# remotetool.net
KiCad netlist of a schematic drawn in EAGLE
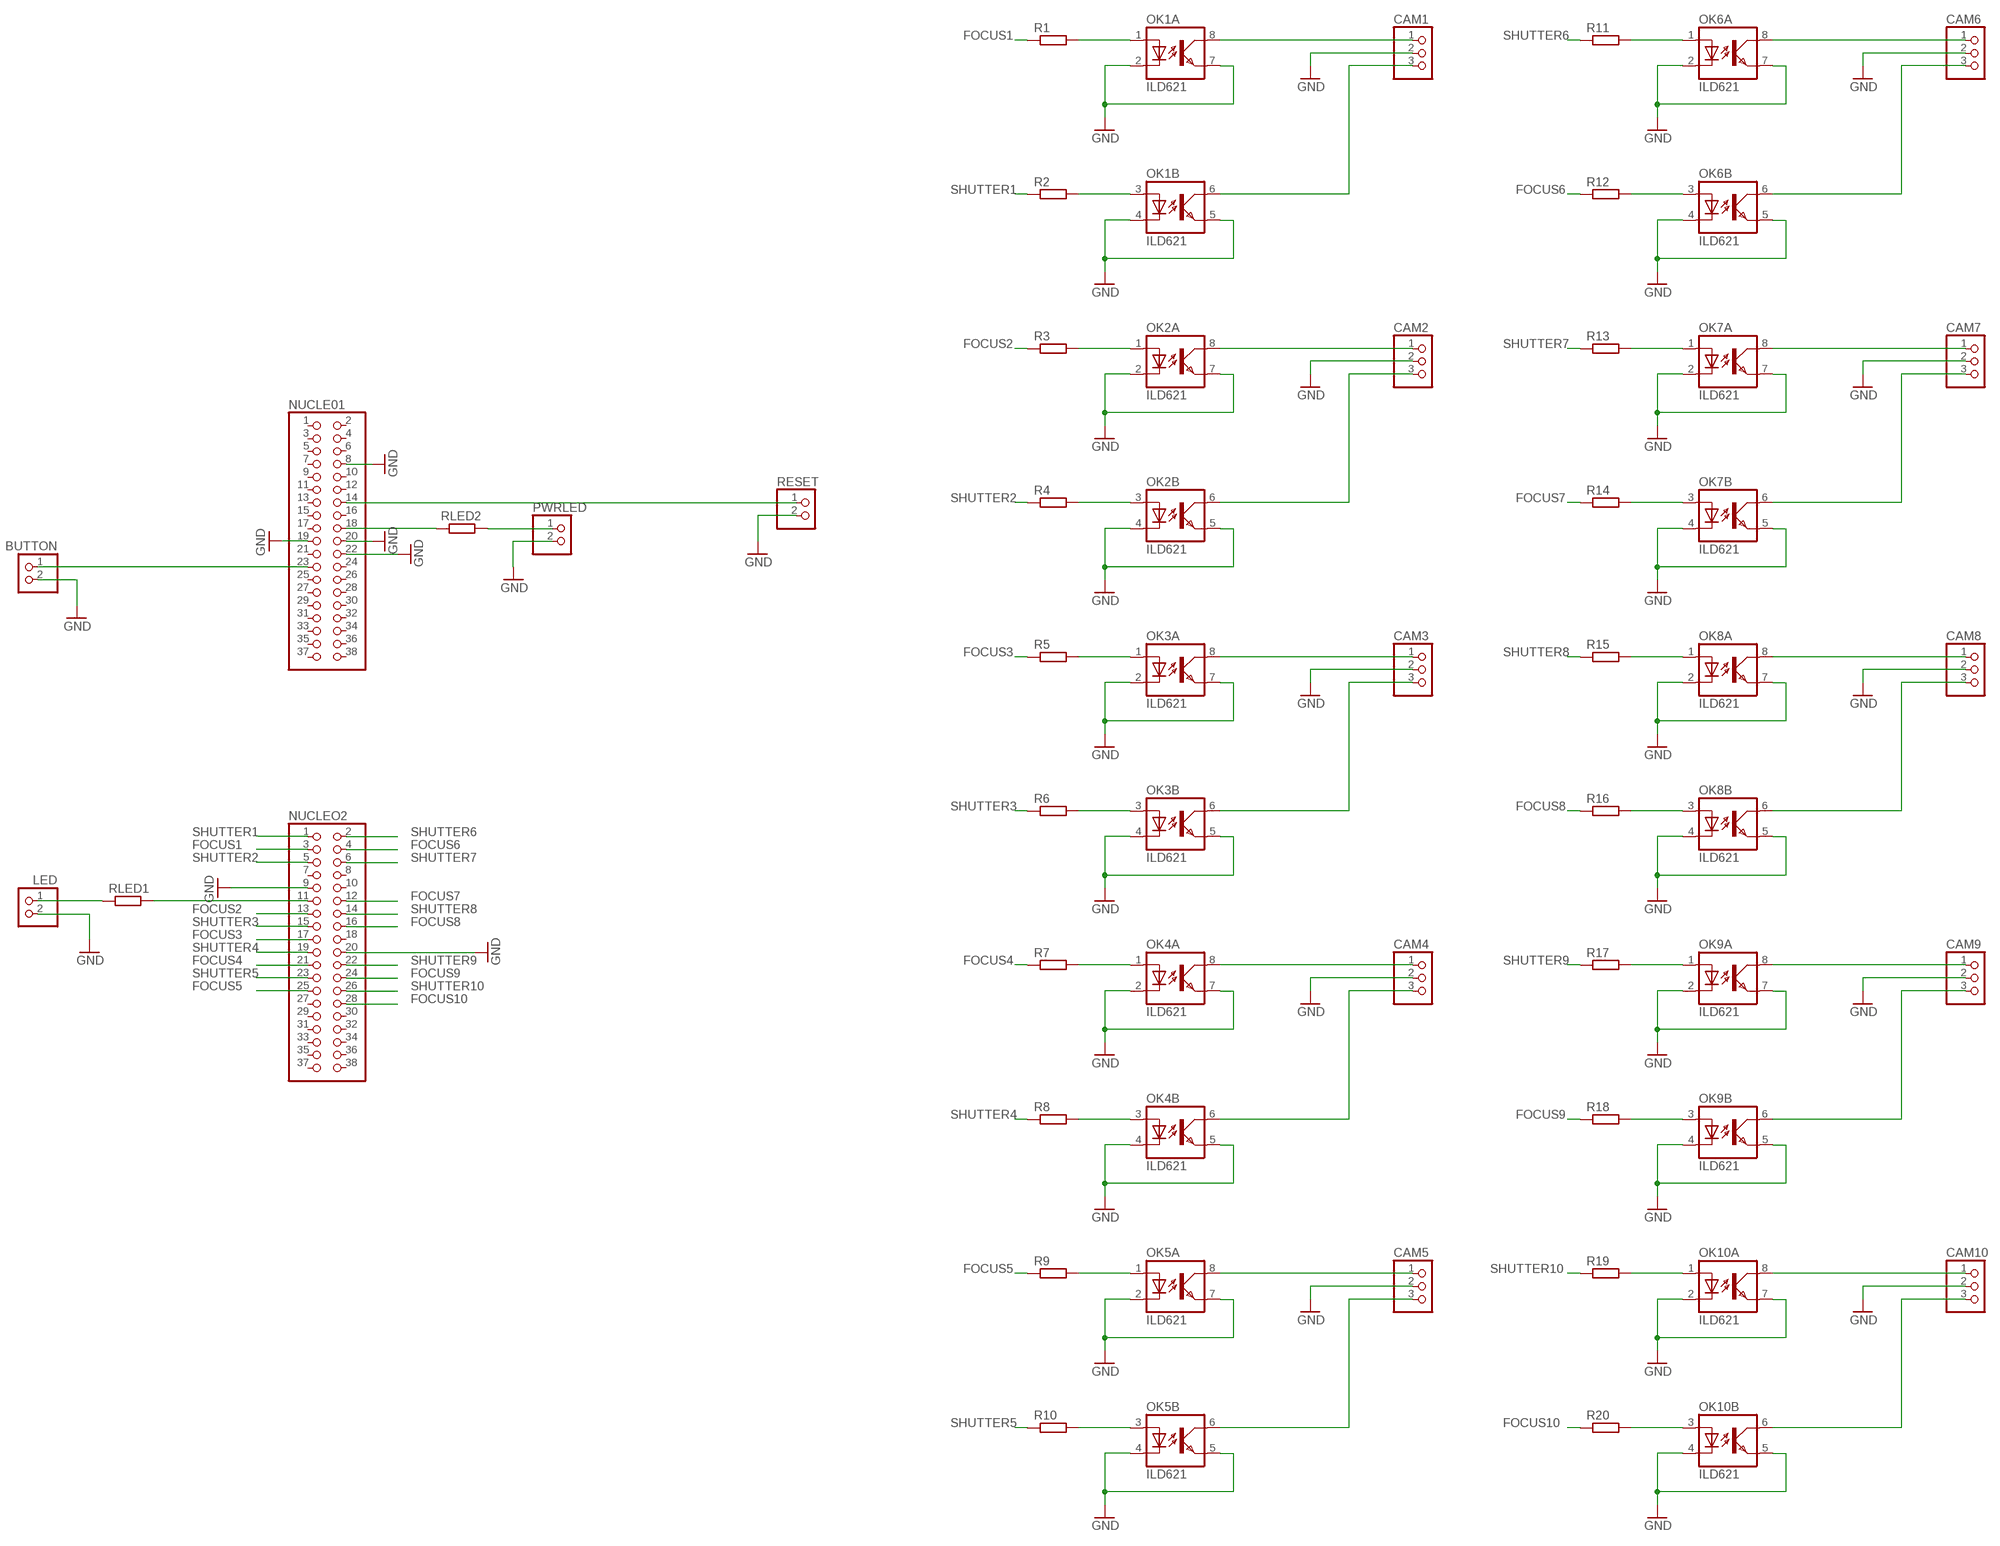
[diagram p0: schematic, sheet 1]

(export (version "E")
  (design (tool "Eeschema 10.0.6"))
  (components
    (comp (ref "BUTTON")
      (value "PINHD-1X2")
      (footprint "eagle-import:1X02")
      (libsource (lib "eagle-import") (part "PINHD-1X2"))
    )
    (comp (ref "CAM1")
      (value "PINHD-1X3")
      (footprint "eagle-import:1X03")
      (libsource (lib "eagle-import") (part "PINHD-1X3"))
    )
    (comp (ref "CAM2")
      (value "PINHD-1X3")
      (footprint "eagle-import:1X03")
      (libsource (lib "eagle-import") (part "PINHD-1X3"))
    )
    (comp (ref "CAM3")
      (value "PINHD-1X3")
      (footprint "eagle-import:1X03")
      (libsource (lib "eagle-import") (part "PINHD-1X3"))
    )
    (comp (ref "CAM4")
      (value "PINHD-1X3")
      (footprint "eagle-import:1X03")
      (libsource (lib "eagle-import") (part "PINHD-1X3"))
    )
    (comp (ref "CAM5")
      (value "PINHD-1X3")
      (footprint "eagle-import:1X03")
      (libsource (lib "eagle-import") (part "PINHD-1X3"))
    )
    (comp (ref "CAM6")
      (value "PINHD-1X3")
      (footprint "eagle-import:1X03")
      (libsource (lib "eagle-import") (part "PINHD-1X3"))
    )
    (comp (ref "CAM7")
      (value "PINHD-1X3")
      (footprint "eagle-import:1X03")
      (libsource (lib "eagle-import") (part "PINHD-1X3"))
    )
    (comp (ref "CAM8")
      (value "PINHD-1X3")
      (footprint "eagle-import:1X03")
      (libsource (lib "eagle-import") (part "PINHD-1X3"))
    )
    (comp (ref "CAM9")
      (value "PINHD-1X3")
      (footprint "eagle-import:1X03")
      (libsource (lib "eagle-import") (part "PINHD-1X3"))
    )
    (comp (ref "CAM10")
      (value "PINHD-1X3")
      (footprint "eagle-import:1X03")
      (libsource (lib "eagle-import") (part "PINHD-1X3"))
    )
    (comp (ref "LED")
      (value "PINHD-1X2")
      (footprint "eagle-import:1X02")
      (libsource (lib "eagle-import") (part "PINHD-1X2"))
    )
    (comp (ref "NUCLE01")
      (value "PINHD-2X19")
      (footprint "eagle-import:2X19")
      (libsource (lib "eagle-import") (part "PINHD-2X19"))
    )
    (comp (ref "NUCLEO2")
      (value "PINHD-2X19")
      (footprint "eagle-import:2X19")
      (libsource (lib "eagle-import") (part "PINHD-2X19"))
    )
    (comp (ref "OK1")
      (value "ILD621")
      (footprint "eagle-import:DIL08")
      (fields (field (name "MF") "VISHAY/TELEFUNKEN"))
      (libsource (lib "eagle-import") (part "ILD621"))
    )
    (comp (ref "OK2")
      (value "ILD621")
      (footprint "eagle-import:DIL08")
      (fields (field (name "MF") "VISHAY/TELEFUNKEN"))
      (libsource (lib "eagle-import") (part "ILD621"))
    )
    (comp (ref "OK3")
      (value "ILD621")
      (footprint "eagle-import:DIL08")
      (fields (field (name "MF") "VISHAY/TELEFUNKEN"))
      (libsource (lib "eagle-import") (part "ILD621"))
    )
    (comp (ref "OK4")
      (value "ILD621")
      (footprint "eagle-import:DIL08")
      (fields (field (name "MF") "VISHAY/TELEFUNKEN"))
      (libsource (lib "eagle-import") (part "ILD621"))
    )
    (comp (ref "OK5")
      (value "ILD621")
      (footprint "eagle-import:DIL08")
      (fields (field (name "MF") "VISHAY/TELEFUNKEN"))
      (libsource (lib "eagle-import") (part "ILD621"))
    )
    (comp (ref "OK6")
      (value "ILD621")
      (footprint "eagle-import:DIL08")
      (fields (field (name "MF") "VISHAY/TELEFUNKEN"))
      (libsource (lib "eagle-import") (part "ILD621"))
    )
    (comp (ref "OK7")
      (value "ILD621")
      (footprint "eagle-import:DIL08")
      (fields (field (name "MF") "VISHAY/TELEFUNKEN"))
      (libsource (lib "eagle-import") (part "ILD621"))
    )
    (comp (ref "OK8")
      (value "ILD621")
      (footprint "eagle-import:DIL08")
      (fields (field (name "MF") "VISHAY/TELEFUNKEN"))
      (libsource (lib "eagle-import") (part "ILD621"))
    )
    (comp (ref "OK9")
      (value "ILD621")
      (footprint "eagle-import:DIL08")
      (fields (field (name "MF") "VISHAY/TELEFUNKEN"))
      (libsource (lib "eagle-import") (part "ILD621"))
    )
    (comp (ref "OK10")
      (value "ILD621")
      (footprint "eagle-import:DIL08")
      (fields (field (name "MF") "VISHAY/TELEFUNKEN"))
      (libsource (lib "eagle-import") (part "ILD621"))
    )
    (comp (ref "PWRLED")
      (value "PINHD-1X2")
      (footprint "eagle-import:1X02")
      (libsource (lib "eagle-import") (part "PINHD-1X2"))
    )
    (comp (ref "R1")
      (value "R-EU_0207/2V")
      (footprint "eagle-import:0207_2V")
      (libsource (lib "eagle-import") (part "R-EU_0207/2V"))
    )
    (comp (ref "R2")
      (value "R-EU_0207/2V")
      (footprint "eagle-import:0207_2V")
      (libsource (lib "eagle-import") (part "R-EU_0207/2V"))
    )
    (comp (ref "R3")
      (value "R-EU_0207/2V")
      (footprint "eagle-import:0207_2V")
      (libsource (lib "eagle-import") (part "R-EU_0207/2V"))
    )
    (comp (ref "R4")
      (value "R-EU_0207/2V")
      (footprint "eagle-import:0207_2V")
      (libsource (lib "eagle-import") (part "R-EU_0207/2V"))
    )
    (comp (ref "R5")
      (value "R-EU_0207/2V")
      (footprint "eagle-import:0207_2V")
      (libsource (lib "eagle-import") (part "R-EU_0207/2V"))
    )
    (comp (ref "R6")
      (value "R-EU_0207/2V")
      (footprint "eagle-import:0207_2V")
      (libsource (lib "eagle-import") (part "R-EU_0207/2V"))
    )
    (comp (ref "R7")
      (value "R-EU_0207/2V")
      (footprint "eagle-import:0207_2V")
      (libsource (lib "eagle-import") (part "R-EU_0207/2V"))
    )
    (comp (ref "R8")
      (value "R-EU_0207/2V")
      (footprint "eagle-import:0207_2V")
      (libsource (lib "eagle-import") (part "R-EU_0207/2V"))
    )
    (comp (ref "R9")
      (value "R-EU_0207/2V")
      (footprint "eagle-import:0207_2V")
      (libsource (lib "eagle-import") (part "R-EU_0207/2V"))
    )
    (comp (ref "R10")
      (value "R-EU_0207/2V")
      (footprint "eagle-import:0207_2V")
      (libsource (lib "eagle-import") (part "R-EU_0207/2V"))
    )
    (comp (ref "R11")
      (value "R-EU_0207/2V")
      (footprint "eagle-import:0207_2V")
      (libsource (lib "eagle-import") (part "R-EU_0207/2V"))
    )
    (comp (ref "R12")
      (value "R-EU_0207/2V")
      (footprint "eagle-import:0207_2V")
      (libsource (lib "eagle-import") (part "R-EU_0207/2V"))
    )
    (comp (ref "R13")
      (value "R-EU_0207/2V")
      (footprint "eagle-import:0207_2V")
      (libsource (lib "eagle-import") (part "R-EU_0207/2V"))
    )
    (comp (ref "R14")
      (value "R-EU_0207/2V")
      (footprint "eagle-import:0207_2V")
      (libsource (lib "eagle-import") (part "R-EU_0207/2V"))
    )
    (comp (ref "R15")
      (value "R-EU_0207/2V")
      (footprint "eagle-import:0207_2V")
      (libsource (lib "eagle-import") (part "R-EU_0207/2V"))
    )
    (comp (ref "R16")
      (value "R-EU_0207/2V")
      (footprint "eagle-import:0207_2V")
      (libsource (lib "eagle-import") (part "R-EU_0207/2V"))
    )
    (comp (ref "R17")
      (value "R-EU_0207/2V")
      (footprint "eagle-import:0207_2V")
      (libsource (lib "eagle-import") (part "R-EU_0207/2V"))
    )
    (comp (ref "R18")
      (value "R-EU_0207/2V")
      (footprint "eagle-import:0207_2V")
      (libsource (lib "eagle-import") (part "R-EU_0207/2V"))
    )
    (comp (ref "R19")
      (value "R-EU_0207/2V")
      (footprint "eagle-import:0207_2V")
      (libsource (lib "eagle-import") (part "R-EU_0207/2V"))
    )
    (comp (ref "R20")
      (value "R-EU_0207/2V")
      (footprint "eagle-import:0207_2V")
      (libsource (lib "eagle-import") (part "R-EU_0207/2V"))
    )
    (comp (ref "RESET")
      (value "PINHD-1X2")
      (footprint "eagle-import:1X02")
      (libsource (lib "eagle-import") (part "PINHD-1X2"))
    )
    (comp (ref "RLED1")
      (value "R-EU_0207/2V")
      (footprint "eagle-import:0207_2V")
      (libsource (lib "eagle-import") (part "R-EU_0207/2V"))
    )
    (comp (ref "RLED2")
      (value "R-EU_0207/2V")
      (footprint "eagle-import:0207_2V")
      (libsource (lib "eagle-import") (part "R-EU_0207/2V"))
    )
  )
  (nets
    (net (code "1") (name "/FOCUS1") (class "Default")
      (node (ref "NUCLEO2") (pin "3") (pinfunction "3_3") (pintype "passive"))
      (node (ref "R1") (pin "1") (pinfunction "1_1") (pintype "passive"))
    )
    (net (code "2") (name "/FOCUS2") (class "Default")
      (node (ref "NUCLEO2") (pin "13") (pinfunction "13_13") (pintype "passive"))
      (node (ref "R3") (pin "1") (pinfunction "1_1") (pintype "passive"))
    )
    (net (code "3") (name "/FOCUS3") (class "Default")
      (node (ref "NUCLEO2") (pin "17") (pinfunction "17_17") (pintype "passive"))
      (node (ref "R5") (pin "1") (pinfunction "1_1") (pintype "passive"))
    )
    (net (code "4") (name "/FOCUS4") (class "Default")
      (node (ref "NUCLEO2") (pin "21") (pinfunction "21_21") (pintype "passive"))
      (node (ref "R7") (pin "1") (pinfunction "1_1") (pintype "passive"))
    )
    (net (code "5") (name "/FOCUS5") (class "Default")
      (node (ref "NUCLEO2") (pin "25") (pinfunction "25_25") (pintype "passive"))
      (node (ref "R9") (pin "1") (pinfunction "1_1") (pintype "passive"))
    )
    (net (code "6") (name "/FOCUS6") (class "Default")
      (node (ref "NUCLEO2") (pin "4") (pinfunction "4_4") (pintype "passive"))
      (node (ref "R12") (pin "1") (pinfunction "1_1") (pintype "passive"))
    )
    (net (code "7") (name "/FOCUS7") (class "Default")
      (node (ref "NUCLEO2") (pin "12") (pinfunction "12_12") (pintype "passive"))
      (node (ref "R14") (pin "1") (pinfunction "1_1") (pintype "passive"))
    )
    (net (code "8") (name "/FOCUS8") (class "Default")
      (node (ref "NUCLEO2") (pin "16") (pinfunction "16_16") (pintype "passive"))
      (node (ref "R16") (pin "1") (pinfunction "1_1") (pintype "passive"))
    )
    (net (code "9") (name "/FOCUS9") (class "Default")
      (node (ref "NUCLEO2") (pin "24") (pinfunction "24_24") (pintype "passive"))
      (node (ref "R18") (pin "1") (pinfunction "1_1") (pintype "passive"))
    )
    (net (code "10") (name "/FOCUS10") (class "Default")
      (node (ref "NUCLEO2") (pin "28") (pinfunction "28_28") (pintype "passive"))
      (node (ref "R20") (pin "1") (pinfunction "1_1") (pintype "passive"))
    )
    (net (code "11") (name "/SHUTTER1") (class "Default")
      (node (ref "NUCLEO2") (pin "1") (pinfunction "1_1") (pintype "passive"))
      (node (ref "R2") (pin "1") (pinfunction "1_1") (pintype "passive"))
    )
    (net (code "12") (name "/SHUTTER2") (class "Default")
      (node (ref "NUCLEO2") (pin "5") (pinfunction "5_5") (pintype "passive"))
      (node (ref "R4") (pin "1") (pinfunction "1_1") (pintype "passive"))
    )
    (net (code "13") (name "/SHUTTER3") (class "Default")
      (node (ref "NUCLEO2") (pin "15") (pinfunction "15_15") (pintype "passive"))
      (node (ref "R6") (pin "1") (pinfunction "1_1") (pintype "passive"))
    )
    (net (code "14") (name "/SHUTTER4") (class "Default")
      (node (ref "NUCLEO2") (pin "19") (pinfunction "19_19") (pintype "passive"))
      (node (ref "R8") (pin "1") (pinfunction "1_1") (pintype "passive"))
    )
    (net (code "15") (name "/SHUTTER5") (class "Default")
      (node (ref "NUCLEO2") (pin "23") (pinfunction "23_23") (pintype "passive"))
      (node (ref "R10") (pin "1") (pinfunction "1_1") (pintype "passive"))
    )
    (net (code "16") (name "/SHUTTER6") (class "Default")
      (node (ref "NUCLEO2") (pin "2") (pinfunction "2_2") (pintype "passive"))
      (node (ref "R11") (pin "1") (pinfunction "1_1") (pintype "passive"))
    )
    (net (code "17") (name "/SHUTTER7") (class "Default")
      (node (ref "NUCLEO2") (pin "6") (pinfunction "6_6") (pintype "passive"))
      (node (ref "R13") (pin "1") (pinfunction "1_1") (pintype "passive"))
    )
    (net (code "18") (name "/SHUTTER8") (class "Default")
      (node (ref "NUCLEO2") (pin "14") (pinfunction "14_14") (pintype "passive"))
      (node (ref "R15") (pin "1") (pinfunction "1_1") (pintype "passive"))
    )
    (net (code "19") (name "/SHUTTER9") (class "Default")
      (node (ref "NUCLEO2") (pin "22") (pinfunction "22_22") (pintype "passive"))
      (node (ref "R17") (pin "1") (pinfunction "1_1") (pintype "passive"))
    )
    (net (code "20") (name "/SHUTTER10") (class "Default")
      (node (ref "NUCLEO2") (pin "26") (pinfunction "26_26") (pintype "passive"))
      (node (ref "R19") (pin "1") (pinfunction "1_1") (pintype "passive"))
    )
    (net (code "21") (name "GND") (class "Default")
      (node (ref "BUTTON") (pin "2") (pinfunction "2_2") (pintype "passive"))
      (node (ref "CAM1") (pin "2") (pinfunction "2_2") (pintype "passive"))
      (node (ref "CAM10") (pin "2") (pinfunction "2_2") (pintype "passive"))
      (node (ref "CAM2") (pin "2") (pinfunction "2_2") (pintype "passive"))
      (node (ref "CAM3") (pin "2") (pinfunction "2_2") (pintype "passive"))
      (node (ref "CAM4") (pin "2") (pinfunction "2_2") (pintype "passive"))
      (node (ref "CAM5") (pin "2") (pinfunction "2_2") (pintype "passive"))
      (node (ref "CAM6") (pin "2") (pinfunction "2_2") (pintype "passive"))
      (node (ref "CAM7") (pin "2") (pinfunction "2_2") (pintype "passive"))
      (node (ref "CAM8") (pin "2") (pinfunction "2_2") (pintype "passive"))
      (node (ref "CAM9") (pin "2") (pinfunction "2_2") (pintype "passive"))
      (node (ref "LED") (pin "2") (pinfunction "2_2") (pintype "passive"))
      (node (ref "NUCLE01") (pin "19") (pinfunction "19_19") (pintype "passive"))
      (node (ref "NUCLE01") (pin "20") (pinfunction "20_20") (pintype "passive"))
      (node (ref "NUCLE01") (pin "22") (pinfunction "22_22") (pintype "passive"))
      (node (ref "NUCLE01") (pin "8") (pinfunction "8_8") (pintype "passive"))
      (node (ref "NUCLEO2") (pin "20") (pinfunction "20_20") (pintype "passive"))
      (node (ref "NUCLEO2") (pin "9") (pinfunction "9_9") (pintype "passive"))
      (node (ref "OK1") (pin "2") (pinfunction "C_2") (pintype "passive"))
      (node (ref "OK1") (pin "4") (pinfunction "C_4") (pintype "passive"))
      (node (ref "OK1") (pin "5") (pinfunction "EMIT_5") (pintype "passive"))
      (node (ref "OK1") (pin "7") (pinfunction "EMIT_7") (pintype "passive"))
      (node (ref "OK10") (pin "2") (pinfunction "C_2") (pintype "passive"))
      (node (ref "OK10") (pin "4") (pinfunction "C_4") (pintype "passive"))
      (node (ref "OK10") (pin "5") (pinfunction "EMIT_5") (pintype "passive"))
      (node (ref "OK10") (pin "7") (pinfunction "EMIT_7") (pintype "passive"))
      (node (ref "OK2") (pin "2") (pinfunction "C_2") (pintype "passive"))
      (node (ref "OK2") (pin "4") (pinfunction "C_4") (pintype "passive"))
      (node (ref "OK2") (pin "5") (pinfunction "EMIT_5") (pintype "passive"))
      (node (ref "OK2") (pin "7") (pinfunction "EMIT_7") (pintype "passive"))
      (node (ref "OK3") (pin "2") (pinfunction "C_2") (pintype "passive"))
      (node (ref "OK3") (pin "4") (pinfunction "C_4") (pintype "passive"))
      (node (ref "OK3") (pin "5") (pinfunction "EMIT_5") (pintype "passive"))
      (node (ref "OK3") (pin "7") (pinfunction "EMIT_7") (pintype "passive"))
      (node (ref "OK4") (pin "2") (pinfunction "C_2") (pintype "passive"))
      (node (ref "OK4") (pin "4") (pinfunction "C_4") (pintype "passive"))
      (node (ref "OK4") (pin "5") (pinfunction "EMIT_5") (pintype "passive"))
      (node (ref "OK4") (pin "7") (pinfunction "EMIT_7") (pintype "passive"))
      (node (ref "OK5") (pin "2") (pinfunction "C_2") (pintype "passive"))
      (node (ref "OK5") (pin "4") (pinfunction "C_4") (pintype "passive"))
      (node (ref "OK5") (pin "5") (pinfunction "EMIT_5") (pintype "passive"))
      (node (ref "OK5") (pin "7") (pinfunction "EMIT_7") (pintype "passive"))
      (node (ref "OK6") (pin "2") (pinfunction "C_2") (pintype "passive"))
      (node (ref "OK6") (pin "4") (pinfunction "C_4") (pintype "passive"))
      (node (ref "OK6") (pin "5") (pinfunction "EMIT_5") (pintype "passive"))
      (node (ref "OK6") (pin "7") (pinfunction "EMIT_7") (pintype "passive"))
      (node (ref "OK7") (pin "2") (pinfunction "C_2") (pintype "passive"))
      (node (ref "OK7") (pin "4") (pinfunction "C_4") (pintype "passive"))
      (node (ref "OK7") (pin "5") (pinfunction "EMIT_5") (pintype "passive"))
      (node (ref "OK7") (pin "7") (pinfunction "EMIT_7") (pintype "passive"))
      (node (ref "OK8") (pin "2") (pinfunction "C_2") (pintype "passive"))
      (node (ref "OK8") (pin "4") (pinfunction "C_4") (pintype "passive"))
      (node (ref "OK8") (pin "5") (pinfunction "EMIT_5") (pintype "passive"))
      (node (ref "OK8") (pin "7") (pinfunction "EMIT_7") (pintype "passive"))
      (node (ref "OK9") (pin "2") (pinfunction "C_2") (pintype "passive"))
      (node (ref "OK9") (pin "4") (pinfunction "C_4") (pintype "passive"))
      (node (ref "OK9") (pin "5") (pinfunction "EMIT_5") (pintype "passive"))
      (node (ref "OK9") (pin "7") (pinfunction "EMIT_7") (pintype "passive"))
      (node (ref "PWRLED") (pin "2") (pinfunction "2_2") (pintype "passive"))
      (node (ref "RESET") (pin "2") (pinfunction "2_2") (pintype "passive"))
    )
    (net (code "22") (name "Net-(BUTTON-Pad1)") (class "Default")
      (node (ref "BUTTON") (pin "1") (pinfunction "1_1") (pintype "passive"))
      (node (ref "NUCLE01") (pin "23") (pinfunction "23_23") (pintype "passive"))
    )
    (net (code "23") (name "Net-(LED-Pad1)") (class "Default")
      (node (ref "LED") (pin "1") (pinfunction "1_1") (pintype "passive"))
      (node (ref "RLED1") (pin "1") (pinfunction "1_1") (pintype "passive"))
    )
    (net (code "24") (name "Net-(NUCLE01-Pad14)") (class "Default")
      (node (ref "NUCLE01") (pin "14") (pinfunction "14_14") (pintype "passive"))
      (node (ref "RESET") (pin "1") (pinfunction "1_1") (pintype "passive"))
    )
    (net (code "25") (name "Net-(NUCLE01-Pad18)") (class "Default")
      (node (ref "NUCLE01") (pin "18") (pinfunction "18_18") (pintype "passive"))
      (node (ref "RLED2") (pin "2") (pinfunction "2_2") (pintype "passive"))
    )
    (net (code "26") (name "Net-(NUCLEO2-Pad11)") (class "Default")
      (node (ref "NUCLEO2") (pin "11") (pinfunction "11_11") (pintype "passive"))
      (node (ref "RLED1") (pin "2") (pinfunction "2_2") (pintype "passive"))
    )
    (net (code "27") (name "Net-(OK1A-A)") (class "Default")
      (node (ref "OK1") (pin "1") (pinfunction "A_1") (pintype "passive"))
      (node (ref "R1") (pin "2") (pinfunction "2_2") (pintype "passive"))
    )
    (net (code "28") (name "Net-(OK1A-COL)") (class "Default")
      (node (ref "CAM1") (pin "1") (pinfunction "1_1") (pintype "passive"))
      (node (ref "OK1") (pin "8") (pinfunction "COL_8") (pintype "passive"))
    )
    (net (code "29") (name "Net-(OK1B-A)") (class "Default")
      (node (ref "OK1") (pin "3") (pinfunction "A_3") (pintype "passive"))
      (node (ref "R2") (pin "2") (pinfunction "2_2") (pintype "passive"))
    )
    (net (code "30") (name "Net-(OK1B-COL)") (class "Default")
      (node (ref "CAM1") (pin "3") (pinfunction "3_3") (pintype "passive"))
      (node (ref "OK1") (pin "6") (pinfunction "COL_6") (pintype "passive"))
    )
    (net (code "31") (name "Net-(OK2A-A)") (class "Default")
      (node (ref "OK2") (pin "1") (pinfunction "A_1") (pintype "passive"))
      (node (ref "R3") (pin "2") (pinfunction "2_2") (pintype "passive"))
    )
    (net (code "32") (name "Net-(OK2A-COL)") (class "Default")
      (node (ref "CAM2") (pin "1") (pinfunction "1_1") (pintype "passive"))
      (node (ref "OK2") (pin "8") (pinfunction "COL_8") (pintype "passive"))
    )
    (net (code "33") (name "Net-(OK2B-A)") (class "Default")
      (node (ref "OK2") (pin "3") (pinfunction "A_3") (pintype "passive"))
      (node (ref "R4") (pin "2") (pinfunction "2_2") (pintype "passive"))
    )
    (net (code "34") (name "Net-(OK2B-COL)") (class "Default")
      (node (ref "CAM2") (pin "3") (pinfunction "3_3") (pintype "passive"))
      (node (ref "OK2") (pin "6") (pinfunction "COL_6") (pintype "passive"))
    )
    (net (code "35") (name "Net-(OK3A-A)") (class "Default")
      (node (ref "OK3") (pin "1") (pinfunction "A_1") (pintype "passive"))
      (node (ref "R5") (pin "2") (pinfunction "2_2") (pintype "passive"))
    )
    (net (code "36") (name "Net-(OK3A-COL)") (class "Default")
      (node (ref "CAM3") (pin "1") (pinfunction "1_1") (pintype "passive"))
      (node (ref "OK3") (pin "8") (pinfunction "COL_8") (pintype "passive"))
    )
    (net (code "37") (name "Net-(OK3B-A)") (class "Default")
      (node (ref "OK3") (pin "3") (pinfunction "A_3") (pintype "passive"))
      (node (ref "R6") (pin "2") (pinfunction "2_2") (pintype "passive"))
    )
    (net (code "38") (name "Net-(OK3B-COL)") (class "Default")
      (node (ref "CAM3") (pin "3") (pinfunction "3_3") (pintype "passive"))
      (node (ref "OK3") (pin "6") (pinfunction "COL_6") (pintype "passive"))
    )
    (net (code "39") (name "Net-(OK4A-A)") (class "Default")
      (node (ref "OK4") (pin "1") (pinfunction "A_1") (pintype "passive"))
      (node (ref "R7") (pin "2") (pinfunction "2_2") (pintype "passive"))
    )
    (net (code "40") (name "Net-(OK4A-COL)") (class "Default")
      (node (ref "CAM4") (pin "1") (pinfunction "1_1") (pintype "passive"))
      (node (ref "OK4") (pin "8") (pinfunction "COL_8") (pintype "passive"))
    )
    (net (code "41") (name "Net-(OK4B-A)") (class "Default")
      (node (ref "OK4") (pin "3") (pinfunction "A_3") (pintype "passive"))
      (node (ref "R8") (pin "2") (pinfunction "2_2") (pintype "passive"))
    )
    (net (code "42") (name "Net-(OK4B-COL)") (class "Default")
      (node (ref "CAM4") (pin "3") (pinfunction "3_3") (pintype "passive"))
      (node (ref "OK4") (pin "6") (pinfunction "COL_6") (pintype "passive"))
    )
    (net (code "43") (name "Net-(OK5A-A)") (class "Default")
      (node (ref "OK5") (pin "1") (pinfunction "A_1") (pintype "passive"))
      (node (ref "R9") (pin "2") (pinfunction "2_2") (pintype "passive"))
    )
    (net (code "44") (name "Net-(OK5A-COL)") (class "Default")
      (node (ref "CAM5") (pin "1") (pinfunction "1_1") (pintype "passive"))
      (node (ref "OK5") (pin "8") (pinfunction "COL_8") (pintype "passive"))
    )
    (net (code "45") (name "Net-(OK5B-A)") (class "Default")
      (node (ref "OK5") (pin "3") (pinfunction "A_3") (pintype "passive"))
      (node (ref "R10") (pin "2") (pinfunction "2_2") (pintype "passive"))
    )
    (net (code "46") (name "Net-(OK5B-COL)") (class "Default")
      (node (ref "CAM5") (pin "3") (pinfunction "3_3") (pintype "passive"))
      (node (ref "OK5") (pin "6") (pinfunction "COL_6") (pintype "passive"))
    )
    (net (code "47") (name "Net-(OK6A-A)") (class "Default")
      (node (ref "OK6") (pin "1") (pinfunction "A_1") (pintype "passive"))
      (node (ref "R11") (pin "2") (pinfunction "2_2") (pintype "passive"))
    )
    (net (code "48") (name "Net-(OK6A-COL)") (class "Default")
      (node (ref "CAM6") (pin "1") (pinfunction "1_1") (pintype "passive"))
      (node (ref "OK6") (pin "8") (pinfunction "COL_8") (pintype "passive"))
    )
    (net (code "49") (name "Net-(OK6B-A)") (class "Default")
      (node (ref "OK6") (pin "3") (pinfunction "A_3") (pintype "passive"))
      (node (ref "R12") (pin "2") (pinfunction "2_2") (pintype "passive"))
    )
    (net (code "50") (name "Net-(OK6B-COL)") (class "Default")
      (node (ref "CAM6") (pin "3") (pinfunction "3_3") (pintype "passive"))
      (node (ref "OK6") (pin "6") (pinfunction "COL_6") (pintype "passive"))
    )
    (net (code "51") (name "Net-(OK7A-A)") (class "Default")
      (node (ref "OK7") (pin "1") (pinfunction "A_1") (pintype "passive"))
      (node (ref "R13") (pin "2") (pinfunction "2_2") (pintype "passive"))
    )
    (net (code "52") (name "Net-(OK7A-COL)") (class "Default")
      (node (ref "CAM7") (pin "1") (pinfunction "1_1") (pintype "passive"))
      (node (ref "OK7") (pin "8") (pinfunction "COL_8") (pintype "passive"))
    )
    (net (code "53") (name "Net-(OK7B-A)") (class "Default")
      (node (ref "OK7") (pin "3") (pinfunction "A_3") (pintype "passive"))
      (node (ref "R14") (pin "2") (pinfunction "2_2") (pintype "passive"))
    )
    (net (code "54") (name "Net-(OK7B-COL)") (class "Default")
      (node (ref "CAM7") (pin "3") (pinfunction "3_3") (pintype "passive"))
      (node (ref "OK7") (pin "6") (pinfunction "COL_6") (pintype "passive"))
    )
    (net (code "55") (name "Net-(OK8A-A)") (class "Default")
      (node (ref "OK8") (pin "1") (pinfunction "A_1") (pintype "passive"))
      (node (ref "R15") (pin "2") (pinfunction "2_2") (pintype "passive"))
    )
    (net (code "56") (name "Net-(OK8A-COL)") (class "Default")
      (node (ref "CAM8") (pin "1") (pinfunction "1_1") (pintype "passive"))
      (node (ref "OK8") (pin "8") (pinfunction "COL_8") (pintype "passive"))
    )
    (net (code "57") (name "Net-(OK8B-A)") (class "Default")
      (node (ref "OK8") (pin "3") (pinfunction "A_3") (pintype "passive"))
      (node (ref "R16") (pin "2") (pinfunction "2_2") (pintype "passive"))
    )
    (net (code "58") (name "Net-(OK8B-COL)") (class "Default")
      (node (ref "CAM8") (pin "3") (pinfunction "3_3") (pintype "passive"))
      (node (ref "OK8") (pin "6") (pinfunction "COL_6") (pintype "passive"))
    )
    (net (code "59") (name "Net-(OK9A-A)") (class "Default")
      (node (ref "OK9") (pin "1") (pinfunction "A_1") (pintype "passive"))
      (node (ref "R17") (pin "2") (pinfunction "2_2") (pintype "passive"))
    )
    (net (code "60") (name "Net-(OK9A-COL)") (class "Default")
      (node (ref "CAM9") (pin "1") (pinfunction "1_1") (pintype "passive"))
      (node (ref "OK9") (pin "8") (pinfunction "COL_8") (pintype "passive"))
    )
    (net (code "61") (name "Net-(OK9B-A)") (class "Default")
      (node (ref "OK9") (pin "3") (pinfunction "A_3") (pintype "passive"))
      (node (ref "R18") (pin "2") (pinfunction "2_2") (pintype "passive"))
    )
    (net (code "62") (name "Net-(OK9B-COL)") (class "Default")
      (node (ref "CAM9") (pin "3") (pinfunction "3_3") (pintype "passive"))
      (node (ref "OK9") (pin "6") (pinfunction "COL_6") (pintype "passive"))
    )
    (net (code "63") (name "Net-(OK10A-A)") (class "Default")
      (node (ref "OK10") (pin "1") (pinfunction "A_1") (pintype "passive"))
      (node (ref "R19") (pin "2") (pinfunction "2_2") (pintype "passive"))
    )
    (net (code "64") (name "Net-(OK10A-COL)") (class "Default")
      (node (ref "CAM10") (pin "1") (pinfunction "1_1") (pintype "passive"))
      (node (ref "OK10") (pin "8") (pinfunction "COL_8") (pintype "passive"))
    )
    (net (code "65") (name "Net-(OK10B-A)") (class "Default")
      (node (ref "OK10") (pin "3") (pinfunction "A_3") (pintype "passive"))
      (node (ref "R20") (pin "2") (pinfunction "2_2") (pintype "passive"))
    )
    (net (code "66") (name "Net-(OK10B-COL)") (class "Default")
      (node (ref "CAM10") (pin "3") (pinfunction "3_3") (pintype "passive"))
      (node (ref "OK10") (pin "6") (pinfunction "COL_6") (pintype "passive"))
    )
    (net (code "67") (name "Net-(PWRLED-Pad1)") (class "Default")
      (node (ref "PWRLED") (pin "1") (pinfunction "1_1") (pintype "passive"))
      (node (ref "RLED2") (pin "1") (pinfunction "1_1") (pintype "passive"))
    )
    (net (code "68") (name "unconnected-(NUCLE01-Pad1)") (class "Default")
      (node (ref "NUCLE01") (pin "1") (pinfunction "1_1") (pintype "passive"))
    )
    (net (code "69") (name "unconnected-(NUCLE01-Pad2)") (class "Default")
      (node (ref "NUCLE01") (pin "2") (pinfunction "2_2") (pintype "passive"))
    )
    (net (code "70") (name "unconnected-(NUCLE01-Pad3)") (class "Default")
      (node (ref "NUCLE01") (pin "3") (pinfunction "3_3") (pintype "passive"))
    )
    (net (code "71") (name "unconnected-(NUCLE01-Pad4)") (class "Default")
      (node (ref "NUCLE01") (pin "4") (pinfunction "4_4") (pintype "passive"))
    )
    (net (code "72") (name "unconnected-(NUCLE01-Pad5)") (class "Default")
      (node (ref "NUCLE01") (pin "5") (pinfunction "5_5") (pintype "passive"))
    )
    (net (code "73") (name "unconnected-(NUCLE01-Pad6)") (class "Default")
      (node (ref "NUCLE01") (pin "6") (pinfunction "6_6") (pintype "passive"))
    )
    (net (code "74") (name "unconnected-(NUCLE01-Pad7)") (class "Default")
      (node (ref "NUCLE01") (pin "7") (pinfunction "7_7") (pintype "passive"))
    )
    (net (code "75") (name "unconnected-(NUCLE01-Pad9)") (class "Default")
      (node (ref "NUCLE01") (pin "9") (pinfunction "9_9") (pintype "passive"))
    )
    (net (code "76") (name "unconnected-(NUCLE01-Pad10)") (class "Default")
      (node (ref "NUCLE01") (pin "10") (pinfunction "10_10") (pintype "passive"))
    )
    (net (code "77") (name "unconnected-(NUCLE01-Pad11)") (class "Default")
      (node (ref "NUCLE01") (pin "11") (pinfunction "11_11") (pintype "passive"))
    )
    (net (code "78") (name "unconnected-(NUCLE01-Pad12)") (class "Default")
      (node (ref "NUCLE01") (pin "12") (pinfunction "12_12") (pintype "passive"))
    )
    (net (code "79") (name "unconnected-(NUCLE01-Pad13)") (class "Default")
      (node (ref "NUCLE01") (pin "13") (pinfunction "13_13") (pintype "passive"))
    )
    (net (code "80") (name "unconnected-(NUCLE01-Pad15)") (class "Default")
      (node (ref "NUCLE01") (pin "15") (pinfunction "15_15") (pintype "passive"))
    )
    (net (code "81") (name "unconnected-(NUCLE01-Pad16)") (class "Default")
      (node (ref "NUCLE01") (pin "16") (pinfunction "16_16") (pintype "passive"))
    )
    (net (code "82") (name "unconnected-(NUCLE01-Pad17)") (class "Default")
      (node (ref "NUCLE01") (pin "17") (pinfunction "17_17") (pintype "passive"))
    )
    (net (code "83") (name "unconnected-(NUCLE01-Pad21)") (class "Default")
      (node (ref "NUCLE01") (pin "21") (pinfunction "21_21") (pintype "passive"))
    )
    (net (code "84") (name "unconnected-(NUCLE01-Pad24)") (class "Default")
      (node (ref "NUCLE01") (pin "24") (pinfunction "24_24") (pintype "passive"))
    )
    (net (code "85") (name "unconnected-(NUCLE01-Pad25)") (class "Default")
      (node (ref "NUCLE01") (pin "25") (pinfunction "25_25") (pintype "passive"))
    )
    (net (code "86") (name "unconnected-(NUCLE01-Pad26)") (class "Default")
      (node (ref "NUCLE01") (pin "26") (pinfunction "26_26") (pintype "passive"))
    )
    (net (code "87") (name "unconnected-(NUCLE01-Pad27)") (class "Default")
      (node (ref "NUCLE01") (pin "27") (pinfunction "27_27") (pintype "passive"))
    )
    (net (code "88") (name "unconnected-(NUCLE01-Pad28)") (class "Default")
      (node (ref "NUCLE01") (pin "28") (pinfunction "28_28") (pintype "passive"))
    )
    (net (code "89") (name "unconnected-(NUCLE01-Pad29)") (class "Default")
      (node (ref "NUCLE01") (pin "29") (pinfunction "29_29") (pintype "passive"))
    )
    (net (code "90") (name "unconnected-(NUCLE01-Pad30)") (class "Default")
      (node (ref "NUCLE01") (pin "30") (pinfunction "30_30") (pintype "passive"))
    )
    (net (code "91") (name "unconnected-(NUCLE01-Pad31)") (class "Default")
      (node (ref "NUCLE01") (pin "31") (pinfunction "31_31") (pintype "passive"))
    )
    (net (code "92") (name "unconnected-(NUCLE01-Pad32)") (class "Default")
      (node (ref "NUCLE01") (pin "32") (pinfunction "32_32") (pintype "passive"))
    )
    (net (code "93") (name "unconnected-(NUCLE01-Pad33)") (class "Default")
      (node (ref "NUCLE01") (pin "33") (pinfunction "33_33") (pintype "passive"))
    )
    (net (code "94") (name "unconnected-(NUCLE01-Pad34)") (class "Default")
      (node (ref "NUCLE01") (pin "34") (pinfunction "34_34") (pintype "passive"))
    )
    (net (code "95") (name "unconnected-(NUCLE01-Pad35)") (class "Default")
      (node (ref "NUCLE01") (pin "35") (pinfunction "35_35") (pintype "passive"))
    )
    (net (code "96") (name "unconnected-(NUCLE01-Pad36)") (class "Default")
      (node (ref "NUCLE01") (pin "36") (pinfunction "36_36") (pintype "passive"))
    )
    (net (code "97") (name "unconnected-(NUCLE01-Pad37)") (class "Default")
      (node (ref "NUCLE01") (pin "37") (pinfunction "37_37") (pintype "passive"))
    )
    (net (code "98") (name "unconnected-(NUCLE01-Pad38)") (class "Default")
      (node (ref "NUCLE01") (pin "38") (pinfunction "38_38") (pintype "passive"))
    )
    (net (code "99") (name "unconnected-(NUCLEO2-Pad7)") (class "Default")
      (node (ref "NUCLEO2") (pin "7") (pinfunction "7_7") (pintype "passive"))
    )
    (net (code "100") (name "unconnected-(NUCLEO2-Pad8)") (class "Default")
      (node (ref "NUCLEO2") (pin "8") (pinfunction "8_8") (pintype "passive"))
    )
    (net (code "101") (name "unconnected-(NUCLEO2-Pad10)") (class "Default")
      (node (ref "NUCLEO2") (pin "10") (pinfunction "10_10") (pintype "passive"))
    )
    (net (code "102") (name "unconnected-(NUCLEO2-Pad18)") (class "Default")
      (node (ref "NUCLEO2") (pin "18") (pinfunction "18_18") (pintype "passive"))
    )
    (net (code "103") (name "unconnected-(NUCLEO2-Pad27)") (class "Default")
      (node (ref "NUCLEO2") (pin "27") (pinfunction "27_27") (pintype "passive"))
    )
    (net (code "104") (name "unconnected-(NUCLEO2-Pad29)") (class "Default")
      (node (ref "NUCLEO2") (pin "29") (pinfunction "29_29") (pintype "passive"))
    )
    (net (code "105") (name "unconnected-(NUCLEO2-Pad30)") (class "Default")
      (node (ref "NUCLEO2") (pin "30") (pinfunction "30_30") (pintype "passive"))
    )
    (net (code "106") (name "unconnected-(NUCLEO2-Pad31)") (class "Default")
      (node (ref "NUCLEO2") (pin "31") (pinfunction "31_31") (pintype "passive"))
    )
    (net (code "107") (name "unconnected-(NUCLEO2-Pad32)") (class "Default")
      (node (ref "NUCLEO2") (pin "32") (pinfunction "32_32") (pintype "passive"))
    )
    (net (code "108") (name "unconnected-(NUCLEO2-Pad33)") (class "Default")
      (node (ref "NUCLEO2") (pin "33") (pinfunction "33_33") (pintype "passive"))
    )
    (net (code "109") (name "unconnected-(NUCLEO2-Pad34)") (class "Default")
      (node (ref "NUCLEO2") (pin "34") (pinfunction "34_34") (pintype "passive"))
    )
    (net (code "110") (name "unconnected-(NUCLEO2-Pad35)") (class "Default")
      (node (ref "NUCLEO2") (pin "35") (pinfunction "35_35") (pintype "passive"))
    )
    (net (code "111") (name "unconnected-(NUCLEO2-Pad36)") (class "Default")
      (node (ref "NUCLEO2") (pin "36") (pinfunction "36_36") (pintype "passive"))
    )
    (net (code "112") (name "unconnected-(NUCLEO2-Pad37)") (class "Default")
      (node (ref "NUCLEO2") (pin "37") (pinfunction "37_37") (pintype "passive"))
    )
    (net (code "113") (name "unconnected-(NUCLEO2-Pad38)") (class "Default")
      (node (ref "NUCLEO2") (pin "38") (pinfunction "38_38") (pintype "passive"))
    )
  )
)
